# ACPowerDistributionDCtoDC.net
KiCad netlist of a schematic drawn in Altium Designer
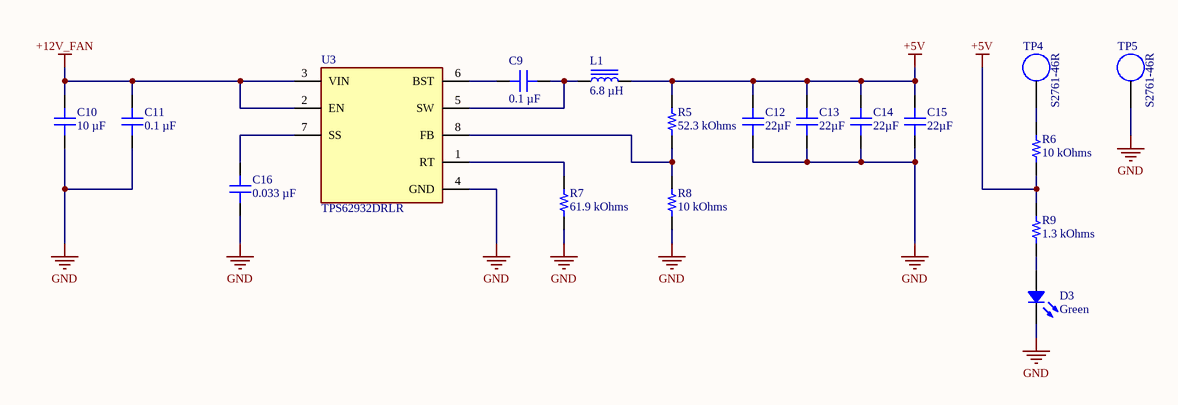
[diagram p0: ACPowerDistributionDCtoDC.SchDoc]

(export (version "E")
  (design (tool "Eeschema 10.0.6"))
  (components
    (comp (ref "C9")
      (value "0.1 µF")
      (footprint "CAP 0603_1608")
      (description "CAP CER 0.1UF 25V X7R 0603")
      (fields
        (field (name "PART NUMBER") "CL10B104KA8WPNC")
        (field (name "CAPACITANCE") "0.1 µF")
        (field (name "MANUFACTURER") "Samsung Electro-Mechanics")
      )
      (libsource (lib "Celestial Altium Library - altium_library") (part "Capacitor"))
    )
    (comp (ref "C10")
      (value "10 µF")
      (footprint "CAP 1210_3225 - 1MM")
      (description "CAP CER 10UF 75V X7R 1210")
      (fields
        (field (name "PART NUMBER") "CGA6P1X7R1N106K250AC")
        (field (name "MANUFACTURER") "TDK Corporation")
      )
      (libsource (lib "Celestial Altium Library - altium_library") (part "Capacitor"))
    )
    (comp (ref "C11")
      (value "0.1 µF")
      (footprint "CAP 0603_1608")
      (description "CAP CER 0.1UF 25V X7R 0603")
      (fields
        (field (name "PART NUMBER") "CL10B104KA8WPNC")
        (field (name "CAPACITANCE") "0.1 µF")
        (field (name "MANUFACTURER") "Samsung Electro-Mechanics")
      )
      (libsource (lib "Celestial Altium Library - altium_library") (part "Capacitor"))
    )
    (comp (ref "C12")
      (value "22µF")
      (footprint "CAP 1210_3225 - 2.8MM")
      (description "CAP CER 22UF 16V X7R 1210")
      (fields (field (name "PART NUMBER") "1210YC226KAT4A") (field (name "MANUFACTURER") "AVX Corporation"))
      (libsource (lib "Celestial Altium Library - altium_library") (part "Capacitor"))
    )
    (comp (ref "C13")
      (value "22µF")
      (footprint "CAP 1210_3225 - 2.8MM")
      (description "CAP CER 22UF 16V X7R 1210")
      (fields (field (name "PART NUMBER") "1210YC226KAT4A") (field (name "MANUFACTURER") "AVX Corporation"))
      (libsource (lib "Celestial Altium Library - altium_library") (part "Capacitor"))
    )
    (comp (ref "C14")
      (value "22µF")
      (footprint "CAP 1210_3225 - 2.8MM")
      (description "CAP CER 22UF 16V X7R 1210")
      (fields (field (name "PART NUMBER") "1210YC226KAT4A") (field (name "MANUFACTURER") "AVX Corporation"))
      (libsource (lib "Celestial Altium Library - altium_library") (part "Capacitor"))
    )
    (comp (ref "C15")
      (value "22µF")
      (footprint "CAP 1210_3225 - 2.8MM")
      (description "CAP CER 22UF 16V X7R 1210")
      (fields (field (name "PART NUMBER") "1210YC226KAT4A") (field (name "MANUFACTURER") "AVX Corporation"))
      (libsource (lib "Celestial Altium Library - altium_library") (part "Capacitor"))
    )
    (comp (ref "C16")
      (value "0.033 µF")
      (footprint "CAP 0603_1608")
      (description "CAP CER 0.033UF 16V X7R 0603")
      (fields
        (field (name "PART NUMBER") "CC0603KRX7R7BB333")
        (field (name "CAPACITANCE") "0.033 µF")
        (field (name "MANUFACTURER") "Yageo")
      )
      (libsource (lib "Celestial Altium Library - altium_library") (part "Capacitor"))
    )
    (comp (ref "D3")
      (value "Green")
      (footprint "LED 0603_1608 GREEN")
      (description "LED GREEN CLEAR 0603 SMD")
      (fields (field (name "PART NUMBER") "150060VS75020") (field (name "MANUFACTURER") "Würth Elektronik"))
      (libsource (lib "Celestial Altium Library - altium_library") (part "LED"))
    )
    (comp (ref "L1")
      (value "6.8 µH")
      (footprint "WURTH WE-LQS 6045")
      (description "FIXED IND 6.8UH 3A 31 MOHM SMD")
      (fields (field (name "PART NUMBER") "74404064068") (field (name "MANUFACTURER") "Würth Elektronik"))
      (libsource (lib "Celestial Altium Library - altium_library") (part "Inductor"))
    )
    (comp (ref "R5")
      (value "52.3 kOhms")
      (footprint "YAGEO RES 0603_1608")
      (description "RES SMD 52.3KOHM 0.1% 1/10W 0603")
      (fields (field (name "PART NUMBER") "RT0603BRE0752K3L") (field (name "MANUFACTURER") "Yageo"))
      (libsource (lib "Celestial Altium Library - altium_library") (part "Resistor"))
    )
    (comp (ref "R6")
      (value "10 kOhms")
      (footprint "RES 0603_1608")
      (description "RES 10K OHM 1% 1/10W 0603")
      (fields
        (field (name "PART NUMBER") "RMCF0603FT10K0")
        (field (name "MANUFACTURER") "Stackpole Electronics Inc")
      )
      (libsource (lib "Celestial Altium Library - altium_library") (part "Resistor"))
    )
    (comp (ref "R7")
      (value "61.9 kOhms")
      (footprint "RES 0603_1608")
      (description "RES 61.9K OHM 1% 1/10W 0603")
      (fields
        (field (name "PART NUMBER") "RMCF0603FT61K9")
        (field (name "MANUFACTURER") "Stackpole Electronics Inc")
      )
      (libsource (lib "Celestial Altium Library - altium_library") (part "Resistor"))
    )
    (comp (ref "R8")
      (value "10 kOhms")
      (footprint "RES 0603_1608")
      (description "RES 10K OHM 1% 1/10W 0603")
      (fields
        (field (name "PART NUMBER") "RMCF0603FT10K0")
        (field (name "MANUFACTURER") "Stackpole Electronics Inc")
      )
      (libsource (lib "Celestial Altium Library - altium_library") (part "Resistor"))
    )
    (comp (ref "R9")
      (value "1.3 kOhms")
      (footprint "RES 0603_1608")
      (description "RES 1.3K OHM 5% 1/10W 0603")
      (fields
        (field (name "PART NUMBER") "RMCF0603JT1K30")
        (field (name "MANUFACTURER") "Stackpole Electronics Inc")
      )
      (libsource (lib "Celestial Altium Library - altium_library") (part "Resistor"))
    )
    (comp (ref "TP4")
      (value "S2761-46R")
      (footprint "S2761-46R")
      (libsource (lib "PersonalLibrary") (part "S2761-46R"))
    )
    (comp (ref "TP5")
      (value "S2761-46R")
      (footprint "S2761-46R")
      (libsource (lib "PersonalLibrary") (part "S2761-46R"))
    )
    (comp (ref "U3")
      (value "TPS62932DRLR")
      (footprint "FP-DRL0008A-MFG")
      (description "3.8-V TO 30-V INPUT, 2-A, 200-KH")
      (libsource (lib "Altium Content Vault") (part "530d7937587d685a4b43e131d046c77"))
    )
  )
  (nets
    (net (code "1") (name "+5V") (class "Default")
      (node (ref "C12") (pin "2") (pinfunction "2_2") (pintype "passive"))
      (node (ref "C13") (pin "2") (pinfunction "2_2") (pintype "passive"))
      (node (ref "C14") (pin "2") (pinfunction "2_2") (pintype "passive"))
      (node (ref "C15") (pin "2") (pinfunction "2_2") (pintype "passive"))
      (node (ref "L1") (pin "2") (pinfunction "2_2") (pintype "passive"))
      (node (ref "R5") (pin "2") (pinfunction "2_2") (pintype "passive"))
      (node (ref "R6") (pin "1") (pinfunction "1_1") (pintype "passive"))
      (node (ref "R9") (pin "2") (pinfunction "2_2") (pintype "passive"))
    )
    (net (code "2") (name "+12V_FAN") (class "Default")
      (node (ref "C10") (pin "2") (pinfunction "2_2") (pintype "passive"))
      (node (ref "C11") (pin "2") (pinfunction "2_2") (pintype "passive"))
      (node (ref "U3") (pin "2") (pinfunction "EN_2") (pintype "passive"))
      (node (ref "U3") (pin "3") (pinfunction "VIN_3") (pintype "power_in"))
    )
    (net (code "3") (name "GND") (class "Default")
      (node (ref "C10") (pin "1") (pinfunction "1_1") (pintype "passive"))
      (node (ref "C11") (pin "1") (pinfunction "1_1") (pintype "passive"))
      (node (ref "C12") (pin "1") (pinfunction "1_1") (pintype "passive"))
      (node (ref "C13") (pin "1") (pinfunction "1_1") (pintype "passive"))
      (node (ref "C14") (pin "1") (pinfunction "1_1") (pintype "passive"))
      (node (ref "C15") (pin "1") (pinfunction "1_1") (pintype "passive"))
      (node (ref "C16") (pin "1") (pinfunction "1_1") (pintype "passive"))
      (node (ref "D3") (pin "2") (pinfunction "2_2") (pintype "passive"))
      (node (ref "R7") (pin "1") (pinfunction "1_1") (pintype "passive"))
      (node (ref "R8") (pin "1") (pinfunction "1_1") (pintype "passive"))
      (node (ref "TP5") (pin "1") (pinfunction "1_1") (pintype "passive"))
      (node (ref "U3") (pin "4") (pinfunction "GND_4") (pintype "power_in"))
    )
    (net (code "4") (name "Net-(D3-Pad1)") (class "Default")
      (node (ref "D3") (pin "1") (pinfunction "1_1") (pintype "passive"))
      (node (ref "R9") (pin "1") (pinfunction "1_1") (pintype "passive"))
    )
    (net (code "5") (name "Net-(R6-Pad2)") (class "Default")
      (node (ref "R6") (pin "2") (pinfunction "2_2") (pintype "passive"))
      (node (ref "TP4") (pin "1") (pinfunction "1_1") (pintype "passive"))
    )
    (net (code "6") (name "Net-(U3-BST)") (class "Default")
      (node (ref "C9") (pin "2") (pinfunction "2_2") (pintype "passive"))
      (node (ref "U3") (pin "6") (pinfunction "BST_6") (pintype "passive"))
    )
    (net (code "7") (name "Net-(U3-FB)") (class "Default")
      (node (ref "R5") (pin "1") (pinfunction "1_1") (pintype "passive"))
      (node (ref "R8") (pin "2") (pinfunction "2_2") (pintype "passive"))
      (node (ref "U3") (pin "8") (pinfunction "FB_8") (pintype "passive"))
    )
    (net (code "8") (name "Net-(U3-RT)") (class "Default")
      (node (ref "R7") (pin "2") (pinfunction "2_2") (pintype "passive"))
      (node (ref "U3") (pin "1") (pinfunction "RT_1") (pintype "passive"))
    )
    (net (code "9") (name "Net-(U3-SS)") (class "Default")
      (node (ref "C16") (pin "2") (pinfunction "2_2") (pintype "passive"))
      (node (ref "U3") (pin "7") (pinfunction "SS_7") (pintype "passive"))
    )
    (net (code "10") (name "Net-(U3-SW)") (class "Default")
      (node (ref "C9") (pin "1") (pinfunction "1_1") (pintype "passive"))
      (node (ref "L1") (pin "1") (pinfunction "1_1") (pintype "passive"))
      (node (ref "U3") (pin "5") (pinfunction "SW_5") (pintype "passive"))
    )
  )
)
